# AP_KACA_Controller.net
KiCad netlist of a schematic drawn in EAGLE
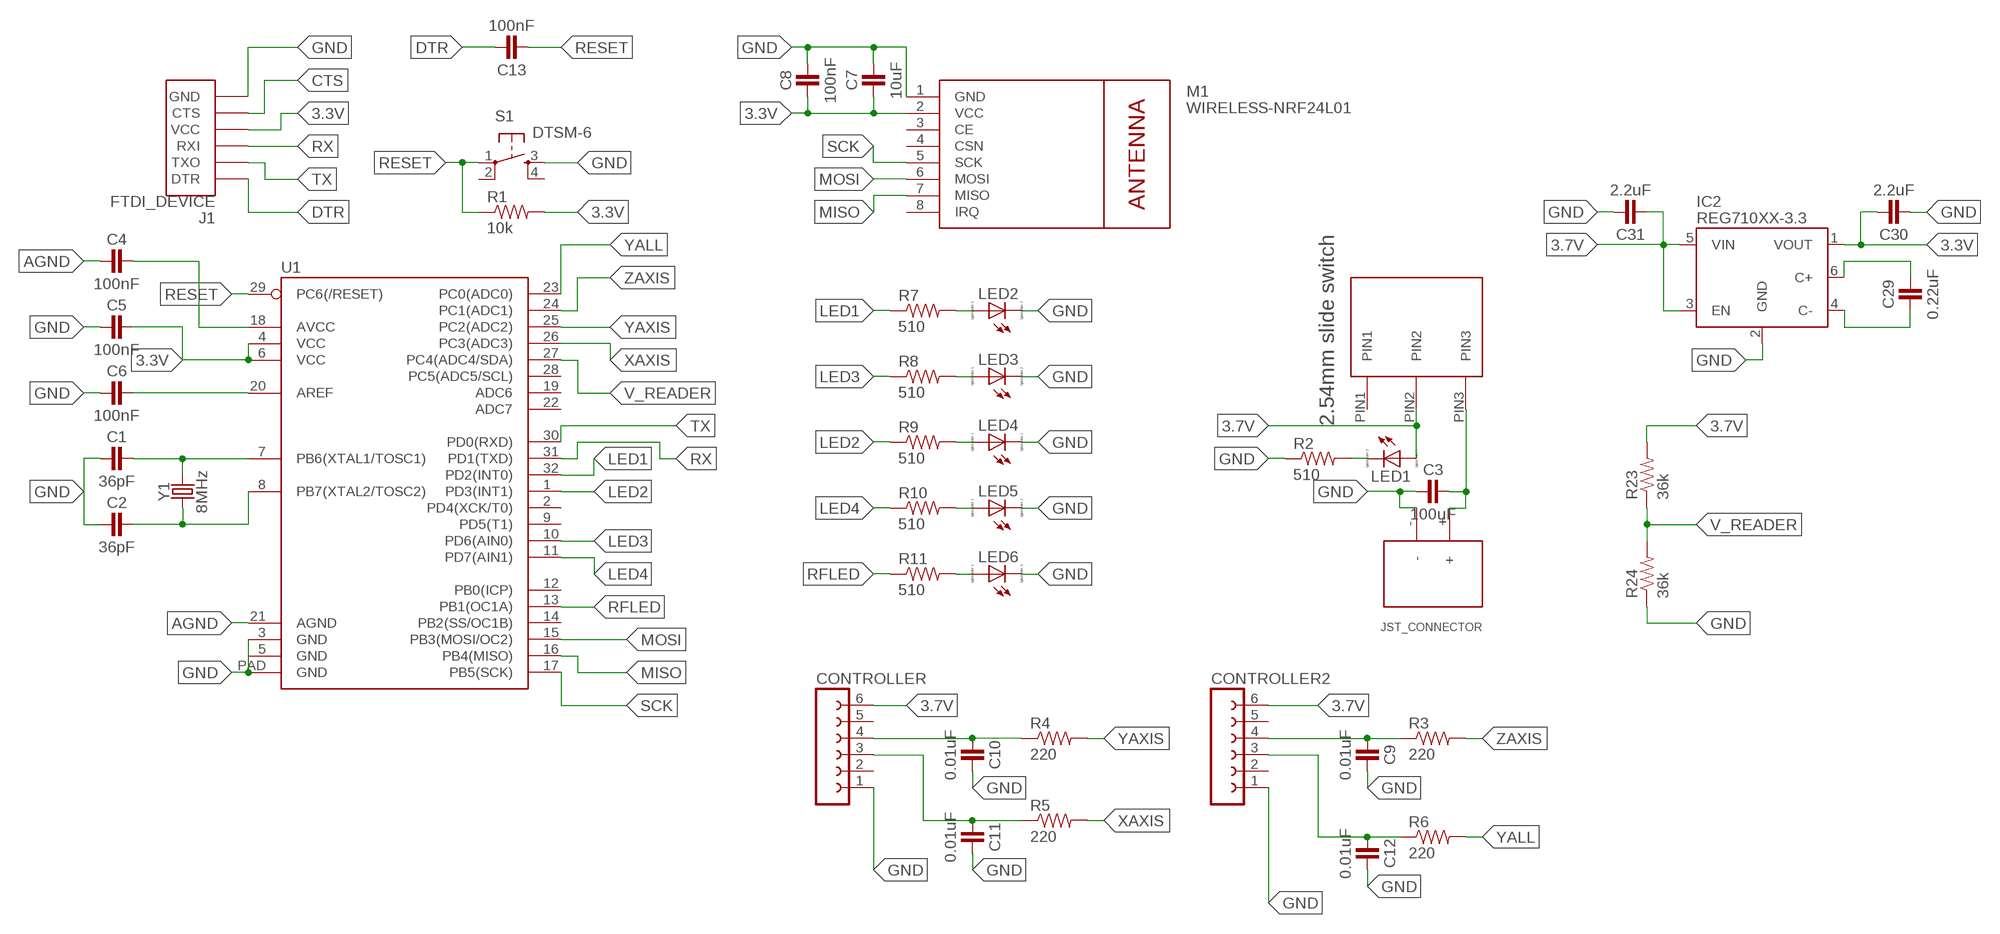
[diagram p0: schematic, sheet 1]

(export (version "E")
  (design (tool "Eeschema 10.0.6"))
  (components
    (comp (ref "C1")
      (value "36pF")
      (footprint "eagle-import:C0603")
      (libsource (lib "eagle-import") (part "CAPACITOR-0603"))
    )
    (comp (ref "C2")
      (value "36pF")
      (footprint "eagle-import:C0603")
      (libsource (lib "eagle-import") (part "CAPACITOR-0603"))
    )
    (comp (ref "C3")
      (value "100uF")
      (footprint "eagle-import:C1206")
      (libsource (lib "eagle-import") (part "CAPACITOR-1206"))
    )
    (comp (ref "C4")
      (value "100nF")
      (footprint "eagle-import:C0603")
      (libsource (lib "eagle-import") (part "CAPACITOR-0603"))
    )
    (comp (ref "C5")
      (value "100nF")
      (footprint "eagle-import:C0603")
      (libsource (lib "eagle-import") (part "CAPACITOR-0603"))
    )
    (comp (ref "C6")
      (value "100nF")
      (footprint "eagle-import:C0603")
      (libsource (lib "eagle-import") (part "CAPACITOR-0603"))
    )
    (comp (ref "C7")
      (value "10uF")
      (footprint "eagle-import:C0603")
      (libsource (lib "eagle-import") (part "CAPACITOR-0603"))
    )
    (comp (ref "C8")
      (value "100nF")
      (footprint "eagle-import:C0603")
      (libsource (lib "eagle-import") (part "CAPACITOR-0603"))
    )
    (comp (ref "C9")
      (value "0.01uF")
      (footprint "eagle-import:C1206")
      (libsource (lib "eagle-import") (part "CAPACITOR-1206"))
    )
    (comp (ref "C10")
      (value "0.01uF")
      (footprint "eagle-import:C1206")
      (libsource (lib "eagle-import") (part "CAPACITOR-1206"))
    )
    (comp (ref "C11")
      (value "0.01uF")
      (footprint "eagle-import:C1206")
      (libsource (lib "eagle-import") (part "CAPACITOR-1206"))
    )
    (comp (ref "C12")
      (value "0.01uF")
      (footprint "eagle-import:C1206")
      (libsource (lib "eagle-import") (part "CAPACITOR-1206"))
    )
    (comp (ref "C13")
      (value "100nF")
      (footprint "eagle-import:C0603")
      (libsource (lib "eagle-import") (part "CAPACITOR-0603"))
    )
    (comp (ref "C29")
      (value "0.22uF")
      (footprint "eagle-import:C1206")
      (libsource (lib "eagle-import") (part "CAPACITOR-1206"))
    )
    (comp (ref "C30")
      (value "2.2uF")
      (footprint "eagle-import:C1206")
      (libsource (lib "eagle-import") (part "CAPACITOR-1206"))
    )
    (comp (ref "C31")
      (value "2.2uF")
      (footprint "eagle-import:C1206")
      (libsource (lib "eagle-import") (part "CAPACITOR-1206"))
    )
    (comp (ref "CONTROLLER")
      (value "FE06-1")
      (footprint "eagle-import:FE06")
      (libsource (lib "eagle-import") (part "FE06-1"))
    )
    (comp (ref "CONTROLLER2")
      (value "FE06-1")
      (footprint "eagle-import:FE06")
      (libsource (lib "eagle-import") (part "FE06-1"))
    )
    (comp (ref "IC2")
      (value "REG710XX-3.3")
      (footprint "eagle-import:SOT23-6")
      (libsource (lib "eagle-import") (part "REG710XX-3.3"))
    )
    (comp (ref "J1")
      (value "FTDI_DEVICE")
      (footprint "eagle-import:FTDI_DEVICE_SIDE")
      (libsource (lib "eagle-import") (part "FTDI_DEVICE"))
    )
    (comp (ref "LED1")
      (value "LED_ESML0603")
      (footprint "eagle-import:LED_SML0603")
      (libsource (lib "eagle-import") (part "LED_ESML0603"))
    )
    (comp (ref "LED2")
      (value "LED_ESML0603")
      (footprint "eagle-import:LED_SML0603")
      (libsource (lib "eagle-import") (part "LED_ESML0603"))
    )
    (comp (ref "LED3")
      (value "LED_ESML0603")
      (footprint "eagle-import:LED_SML0603")
      (libsource (lib "eagle-import") (part "LED_ESML0603"))
    )
    (comp (ref "LED4")
      (value "LED_ESML0603")
      (footprint "eagle-import:LED_SML0603")
      (libsource (lib "eagle-import") (part "LED_ESML0603"))
    )
    (comp (ref "LED5")
      (value "LED_ESML0603")
      (footprint "eagle-import:LED_SML0603")
      (libsource (lib "eagle-import") (part "LED_ESML0603"))
    )
    (comp (ref "LED6")
      (value "LED_ESML0603")
      (footprint "eagle-import:LED_SML0603")
      (libsource (lib "eagle-import") (part "LED_ESML0603"))
    )
    (comp (ref "M1")
      (value "WIRELESS-NRF24L01")
      (footprint "eagle-import:WIRELESS-NRF24L01")
      (libsource (lib "eagle-import") (part "WIRELESS-NRF24L01"))
    )
    (comp (ref "R1")
      (value "10k")
      (footprint "eagle-import:0603")
      (libsource (lib "eagle-import") (part "10.5KOHM1/10W1%(0603)"))
    )
    (comp (ref "R2")
      (value "510")
      (footprint "eagle-import:0603")
      (libsource (lib "eagle-import") (part "10.5KOHM1/10W1%(0603)"))
    )
    (comp (ref "R3")
      (value "220")
      (footprint "eagle-import:0603")
      (libsource (lib "eagle-import") (part "10.5KOHM1/10W1%(0603)"))
    )
    (comp (ref "R4")
      (value "220")
      (footprint "eagle-import:0603")
      (libsource (lib "eagle-import") (part "10.5KOHM1/10W1%(0603)"))
    )
    (comp (ref "R5")
      (value "220")
      (footprint "eagle-import:0603")
      (libsource (lib "eagle-import") (part "10.5KOHM1/10W1%(0603)"))
    )
    (comp (ref "R6")
      (value "220")
      (footprint "eagle-import:0603")
      (libsource (lib "eagle-import") (part "10.5KOHM1/10W1%(0603)"))
    )
    (comp (ref "R7")
      (value "510")
      (footprint "eagle-import:0603")
      (libsource (lib "eagle-import") (part "10.5KOHM1/10W1%(0603)"))
    )
    (comp (ref "R8")
      (value "510")
      (footprint "eagle-import:0603")
      (libsource (lib "eagle-import") (part "10.5KOHM1/10W1%(0603)"))
    )
    (comp (ref "R9")
      (value "510")
      (footprint "eagle-import:0603")
      (libsource (lib "eagle-import") (part "10.5KOHM1/10W1%(0603)"))
    )
    (comp (ref "R10")
      (value "510")
      (footprint "eagle-import:0603")
      (libsource (lib "eagle-import") (part "10.5KOHM1/10W1%(0603)"))
    )
    (comp (ref "R11")
      (value "510")
      (footprint "eagle-import:0603")
      (libsource (lib "eagle-import") (part "10.5KOHM1/10W1%(0603)"))
    )
    (comp (ref "R23")
      (value "36k")
      (footprint "eagle-import:0603")
      (libsource (lib "eagle-import") (part "10.5KOHM1/10W1%(0603)"))
    )
    (comp (ref "R24")
      (value "36k")
      (footprint "eagle-import:0603")
      (libsource (lib "eagle-import") (part "10.5KOHM1/10W1%(0603)"))
    )
    (comp (ref "S1")
      (value "DTSM-6")
      (footprint "eagle-import:DTSM-6")
      (libsource (lib "eagle-import") (part "DTSM-6"))
    )
    (comp (ref "U$1")
      (value "TS02_SWITCH")
      (footprint "eagle-import:TS02_SWITCH")
      (libsource (lib "eagle-import") (part "TS02_SWITCH"))
    )
    (comp (ref "U$2")
      (value "JST_CONNECTOR_FEMALE")
      (footprint "eagle-import:JST_CONNECTOR_FEMALE")
      (libsource (lib "eagle-import") (part "JST_CONNECTOR_FEMALE"))
    )
    (comp (ref "U1")
      (value "ATMEGA328P_MLFMLF32")
      (footprint "eagle-import:MLF32-PAD")
      (libsource (lib "eagle-import") (part "ATMEGA328P_MLFMLF32"))
    )
    (comp (ref "Y1")
      (value "8MHz")
      (footprint "eagle-import:HC49UP")
      (libsource (lib "eagle-import") (part "CRYSTAL-8MHZSMD-HC49UP"))
    )
  )
  (nets
    (net (code "1") (name "3.3V") (class "Default")
      (node (ref "C30") (pin "2") (pinfunction "2_2") (pintype "passive"))
      (node (ref "C5") (pin "2") (pinfunction "2_2") (pintype "passive"))
      (node (ref "C7") (pin "1") (pinfunction "1_1") (pintype "passive"))
      (node (ref "C8") (pin "1") (pinfunction "1_1") (pintype "passive"))
      (node (ref "IC2") (pin "1") (pinfunction "VOUT_1") (pintype "power_in"))
      (node (ref "J1") (pin "P$4") (pinfunction "VCC_P$4") (pintype "bidirectional"))
      (node (ref "M1") (pin "2") (pinfunction "VCC_2") (pintype "power_in"))
      (node (ref "R1") (pin "2") (pinfunction "2_2") (pintype "passive"))
      (node (ref "U1") (pin "4") (pinfunction "VCC_4") (pintype "bidirectional"))
      (node (ref "U1") (pin "6") (pinfunction "VCC_6") (pintype "bidirectional"))
    )
    (net (code "2") (name "3.7V") (class "Default")
      (node (ref "C31") (pin "1") (pinfunction "1_1") (pintype "passive"))
      (node (ref "CONTROLLER") (pin "6") (pinfunction "6_6") (pintype "passive"))
      (node (ref "CONTROLLER2") (pin "6") (pinfunction "6_6") (pintype "passive"))
      (node (ref "IC2") (pin "3") (pinfunction "EN_3") (pintype "passive"))
      (node (ref "IC2") (pin "5") (pinfunction "VIN_5") (pintype "power_in"))
      (node (ref "LED1") (pin "A") (pinfunction "A_A") (pintype "passive"))
      (node (ref "R23") (pin "2") (pinfunction "2_2") (pintype "passive"))
      (node (ref "U$1") (pin "PIN2") (pinfunction "PIN2_PIN2") (pintype "bidirectional"))
    )
    (net (code "3") (name "AGND") (class "Default")
      (node (ref "C4") (pin "1") (pinfunction "1_1") (pintype "passive"))
      (node (ref "U1") (pin "21") (pinfunction "AGND_21") (pintype "bidirectional"))
    )
    (net (code "4") (name "CTS") (class "Default")
      (node (ref "J1") (pin "P$5") (pinfunction "CTS_P$5") (pintype "bidirectional"))
    )
    (net (code "5") (name "DTR") (class "Default")
      (node (ref "C13") (pin "2") (pinfunction "2_2") (pintype "passive"))
      (node (ref "J1") (pin "P$1") (pinfunction "DTR_P$1") (pintype "bidirectional"))
    )
    (net (code "6") (name "GND") (class "Default")
      (node (ref "C1") (pin "1") (pinfunction "1_1") (pintype "passive"))
      (node (ref "C10") (pin "2") (pinfunction "2_2") (pintype "passive"))
      (node (ref "C11") (pin "2") (pinfunction "2_2") (pintype "passive"))
      (node (ref "C12") (pin "2") (pinfunction "2_2") (pintype "passive"))
      (node (ref "C2") (pin "1") (pinfunction "1_1") (pintype "passive"))
      (node (ref "C3") (pin "1") (pinfunction "1_1") (pintype "passive"))
      (node (ref "C30") (pin "1") (pinfunction "1_1") (pintype "passive"))
      (node (ref "C31") (pin "2") (pinfunction "2_2") (pintype "passive"))
      (node (ref "C5") (pin "1") (pinfunction "1_1") (pintype "passive"))
      (node (ref "C6") (pin "1") (pinfunction "1_1") (pintype "passive"))
      (node (ref "C7") (pin "2") (pinfunction "2_2") (pintype "passive"))
      (node (ref "C8") (pin "2") (pinfunction "2_2") (pintype "passive"))
      (node (ref "C9") (pin "2") (pinfunction "2_2") (pintype "passive"))
      (node (ref "CONTROLLER") (pin "1") (pinfunction "1_1") (pintype "passive"))
      (node (ref "CONTROLLER2") (pin "1") (pinfunction "1_1") (pintype "passive"))
      (node (ref "IC2") (pin "2") (pinfunction "GND_2") (pintype "power_in"))
      (node (ref "J1") (pin "P$6") (pinfunction "GND_P$6") (pintype "bidirectional"))
      (node (ref "LED2") (pin "C") (pinfunction "C_C") (pintype "passive"))
      (node (ref "LED3") (pin "C") (pinfunction "C_C") (pintype "passive"))
      (node (ref "LED4") (pin "C") (pinfunction "C_C") (pintype "passive"))
      (node (ref "LED5") (pin "C") (pinfunction "C_C") (pintype "passive"))
      (node (ref "LED6") (pin "C") (pinfunction "C_C") (pintype "passive"))
      (node (ref "M1") (pin "1") (pinfunction "GND_1") (pintype "power_in"))
      (node (ref "R2") (pin "1") (pinfunction "1_1") (pintype "passive"))
      (node (ref "R24") (pin "1") (pinfunction "1_1") (pintype "passive"))
      (node (ref "S1") (pin "3") (pinfunction "3_3") (pintype "passive"))
      (node (ref "U$2") (pin "-") (pinfunction "-_-") (pintype "bidirectional"))
      (node (ref "U1") (pin "3") (pinfunction "GND_3") (pintype "bidirectional"))
      (node (ref "U1") (pin "PAD") (pinfunction "GND_PAD") (pintype "bidirectional"))
    )
    (net (code "7") (name "LED1") (class "Default")
      (node (ref "R7") (pin "1") (pinfunction "1_1") (pintype "passive"))
      (node (ref "U1") (pin "32") (pinfunction "PD2(INT0)_32") (pintype "bidirectional"))
    )
    (net (code "8") (name "LED2") (class "Default")
      (node (ref "R9") (pin "1") (pinfunction "1_1") (pintype "passive"))
      (node (ref "U1") (pin "1") (pinfunction "PD3(INT1)_1") (pintype "bidirectional"))
    )
    (net (code "9") (name "LED3") (class "Default")
      (node (ref "R8") (pin "1") (pinfunction "1_1") (pintype "passive"))
      (node (ref "U1") (pin "10") (pinfunction "PD6(AIN0)_10") (pintype "bidirectional"))
    )
    (net (code "10") (name "LED4") (class "Default")
      (node (ref "R10") (pin "1") (pinfunction "1_1") (pintype "passive"))
      (node (ref "U1") (pin "11") (pinfunction "PD7(AIN1)_11") (pintype "bidirectional"))
    )
    (net (code "11") (name "MISO") (class "Default")
      (node (ref "M1") (pin "7") (pinfunction "MISO_7") (pintype "bidirectional"))
      (node (ref "U1") (pin "16") (pinfunction "PB4(MISO)_16") (pintype "bidirectional"))
    )
    (net (code "12") (name "MOSI") (class "Default")
      (node (ref "M1") (pin "6") (pinfunction "MOSI_6") (pintype "bidirectional"))
      (node (ref "U1") (pin "15") (pinfunction "PB3(MOSI/OC2)_15") (pintype "bidirectional"))
    )
    (net (code "13") (name "Net-(C3-Pad2)") (class "Default")
      (node (ref "C3") (pin "2") (pinfunction "2_2") (pintype "passive"))
      (node (ref "U$1") (pin "PIN3") (pinfunction "PIN3_PIN3") (pintype "bidirectional"))
      (node (ref "U$2") (pin "+") (pinfunction "+_+") (pintype "bidirectional"))
    )
    (net (code "14") (name "Net-(C10-Pad1)") (class "Default")
      (node (ref "C10") (pin "1") (pinfunction "1_1") (pintype "passive"))
      (node (ref "CONTROLLER") (pin "4") (pinfunction "4_4") (pintype "passive"))
      (node (ref "R4") (pin "1") (pinfunction "1_1") (pintype "passive"))
    )
    (net (code "15") (name "Net-(C11-Pad1)") (class "Default")
      (node (ref "C11") (pin "1") (pinfunction "1_1") (pintype "passive"))
      (node (ref "CONTROLLER") (pin "3") (pinfunction "3_3") (pintype "passive"))
      (node (ref "R5") (pin "1") (pinfunction "1_1") (pintype "passive"))
    )
    (net (code "16") (name "Net-(C12-Pad1)") (class "Default")
      (node (ref "C12") (pin "1") (pinfunction "1_1") (pintype "passive"))
      (node (ref "CONTROLLER2") (pin "3") (pinfunction "3_3") (pintype "passive"))
      (node (ref "R6") (pin "1") (pinfunction "1_1") (pintype "passive"))
    )
    (net (code "17") (name "Net-(IC2-C+)") (class "Default")
      (node (ref "C29") (pin "2") (pinfunction "2_2") (pintype "passive"))
      (node (ref "IC2") (pin "6") (pinfunction "C+_6") (pintype "passive"))
    )
    (net (code "18") (name "Net-(IC2-C-)") (class "Default")
      (node (ref "C29") (pin "1") (pinfunction "1_1") (pintype "passive"))
      (node (ref "IC2") (pin "4") (pinfunction "C-_4") (pintype "passive"))
    )
    (net (code "19") (name "Net-(LED1-PadC)") (class "Default")
      (node (ref "LED1") (pin "C") (pinfunction "C_C") (pintype "passive"))
      (node (ref "R2") (pin "2") (pinfunction "2_2") (pintype "passive"))
    )
    (net (code "20") (name "Net-(LED2-PadA)") (class "Default")
      (node (ref "LED2") (pin "A") (pinfunction "A_A") (pintype "passive"))
      (node (ref "R7") (pin "2") (pinfunction "2_2") (pintype "passive"))
    )
    (net (code "21") (name "Net-(LED3-PadA)") (class "Default")
      (node (ref "LED3") (pin "A") (pinfunction "A_A") (pintype "passive"))
      (node (ref "R8") (pin "2") (pinfunction "2_2") (pintype "passive"))
    )
    (net (code "22") (name "Net-(LED4-PadA)") (class "Default")
      (node (ref "LED4") (pin "A") (pinfunction "A_A") (pintype "passive"))
      (node (ref "R9") (pin "2") (pinfunction "2_2") (pintype "passive"))
    )
    (net (code "23") (name "Net-(LED5-PadA)") (class "Default")
      (node (ref "LED5") (pin "A") (pinfunction "A_A") (pintype "passive"))
      (node (ref "R10") (pin "2") (pinfunction "2_2") (pintype "passive"))
    )
    (net (code "24") (name "Net-(LED6-PadA)") (class "Default")
      (node (ref "LED6") (pin "A") (pinfunction "A_A") (pintype "passive"))
      (node (ref "R11") (pin "2") (pinfunction "2_2") (pintype "passive"))
    )
    (net (code "25") (name "Net-(U1-AREF)") (class "Default")
      (node (ref "C6") (pin "2") (pinfunction "2_2") (pintype "passive"))
      (node (ref "U1") (pin "20") (pinfunction "AREF_20") (pintype "bidirectional"))
    )
    (net (code "26") (name "Net-(U1-AVCC)") (class "Default")
      (node (ref "C4") (pin "2") (pinfunction "2_2") (pintype "passive"))
      (node (ref "U1") (pin "18") (pinfunction "AVCC_18") (pintype "bidirectional"))
    )
    (net (code "27") (name "Net-(U1-PB6(XTAL1{slash}TOSC1))") (class "Default")
      (node (ref "C1") (pin "2") (pinfunction "2_2") (pintype "passive"))
      (node (ref "U1") (pin "7") (pinfunction "PB6(XTAL1/TOSC1)_7") (pintype "bidirectional"))
      (node (ref "Y1") (pin "2") (pinfunction "2_2") (pintype "passive"))
    )
    (net (code "28") (name "Net-(U1-PB7(XTAL2{slash}TOSC2))") (class "Default")
      (node (ref "C2") (pin "2") (pinfunction "2_2") (pintype "passive"))
      (node (ref "U1") (pin "8") (pinfunction "PB7(XTAL2/TOSC2)_8") (pintype "bidirectional"))
      (node (ref "Y1") (pin "1") (pinfunction "1_1") (pintype "passive"))
    )
    (net (code "29") (name "RESET") (class "Default")
      (node (ref "C13") (pin "1") (pinfunction "1_1") (pintype "passive"))
      (node (ref "R1") (pin "1") (pinfunction "1_1") (pintype "passive"))
      (node (ref "S1") (pin "1") (pinfunction "1_1") (pintype "passive"))
      (node (ref "U1") (pin "29") (pinfunction "PC6(/RESET)_29") (pintype "bidirectional"))
    )
    (net (code "30") (name "RFLED") (class "Default")
      (node (ref "R11") (pin "1") (pinfunction "1_1") (pintype "passive"))
      (node (ref "U1") (pin "13") (pinfunction "PB1(OC1A)_13") (pintype "bidirectional"))
    )
    (net (code "31") (name "RX") (class "Default")
      (node (ref "J1") (pin "P$3") (pinfunction "RXI_P$3") (pintype "bidirectional"))
      (node (ref "U1") (pin "31") (pinfunction "PD1(TXD)_31") (pintype "bidirectional"))
    )
    (net (code "32") (name "SCK") (class "Default")
      (node (ref "M1") (pin "5") (pinfunction "SCK_5") (pintype "bidirectional"))
      (node (ref "U1") (pin "17") (pinfunction "PB5(SCK)_17") (pintype "bidirectional"))
    )
    (net (code "33") (name "TX") (class "Default")
      (node (ref "J1") (pin "P$2") (pinfunction "TXO_P$2") (pintype "bidirectional"))
      (node (ref "U1") (pin "30") (pinfunction "PD0(RXD)_30") (pintype "bidirectional"))
    )
    (net (code "34") (name "V_READER") (class "Default")
      (node (ref "R23") (pin "1") (pinfunction "1_1") (pintype "passive"))
      (node (ref "R24") (pin "2") (pinfunction "2_2") (pintype "passive"))
      (node (ref "U1") (pin "27") (pinfunction "PC4(ADC4/SDA)_27") (pintype "bidirectional"))
    )
    (net (code "35") (name "XAXIS") (class "Default")
      (node (ref "R5") (pin "2") (pinfunction "2_2") (pintype "passive"))
      (node (ref "U1") (pin "26") (pinfunction "PC3(ADC3)_26") (pintype "bidirectional"))
    )
    (net (code "36") (name "YALL") (class "Default")
      (node (ref "R6") (pin "2") (pinfunction "2_2") (pintype "passive"))
      (node (ref "U1") (pin "23") (pinfunction "PC0(ADC0)_23") (pintype "bidirectional"))
    )
    (net (code "37") (name "YAXIS") (class "Default")
      (node (ref "R4") (pin "2") (pinfunction "2_2") (pintype "passive"))
      (node (ref "U1") (pin "25") (pinfunction "PC2(ADC2)_25") (pintype "bidirectional"))
    )
    (net (code "38") (name "ZAXIS") (class "Default")
      (node (ref "C9") (pin "1") (pinfunction "1_1") (pintype "passive"))
      (node (ref "CONTROLLER2") (pin "4") (pinfunction "4_4") (pintype "passive"))
      (node (ref "R3") (pin "1") (pinfunction "1_1") (pintype "passive"))
      (node (ref "R3") (pin "2") (pinfunction "2_2") (pintype "passive"))
      (node (ref "U1") (pin "24") (pinfunction "PC1(ADC1)_24") (pintype "bidirectional"))
    )
    (net (code "39") (name "unconnected-(CONTROLLER-Pad2)") (class "Default")
      (node (ref "CONTROLLER") (pin "2") (pinfunction "2_2") (pintype "passive"))
    )
    (net (code "40") (name "unconnected-(CONTROLLER-Pad5)") (class "Default")
      (node (ref "CONTROLLER") (pin "5") (pinfunction "5_5") (pintype "passive"))
    )
    (net (code "41") (name "unconnected-(CONTROLLER2-Pad2)") (class "Default")
      (node (ref "CONTROLLER2") (pin "2") (pinfunction "2_2") (pintype "passive"))
    )
    (net (code "42") (name "unconnected-(CONTROLLER2-Pad5)") (class "Default")
      (node (ref "CONTROLLER2") (pin "5") (pinfunction "5_5") (pintype "passive"))
    )
    (net (code "43") (name "unconnected-(M1-CE-Pad3)") (class "Default")
      (node (ref "M1") (pin "3") (pinfunction "CE_3") (pintype "bidirectional"))
    )
    (net (code "44") (name "unconnected-(M1-CSN-Pad4)") (class "Default")
      (node (ref "M1") (pin "4") (pinfunction "CSN_4") (pintype "bidirectional"))
    )
    (net (code "45") (name "unconnected-(M1-IRQ-Pad8)") (class "Default")
      (node (ref "M1") (pin "8") (pinfunction "IRQ_8") (pintype "bidirectional"))
    )
    (net (code "46") (name "unconnected-(S1-Pad2)") (class "Default")
      (node (ref "S1") (pin "2") (pinfunction "2_2") (pintype "passive"))
    )
    (net (code "47") (name "unconnected-(S1-Pad4)") (class "Default")
      (node (ref "S1") (pin "4") (pinfunction "4_4") (pintype "passive"))
    )
    (net (code "48") (name "unconnected-(U$1-PadPIN1)") (class "Default")
      (node (ref "U$1") (pin "PIN1") (pinfunction "PIN1_PIN1") (pintype "bidirectional"))
    )
    (net (code "49") (name "unconnected-(U1-ADC6-Pad19)") (class "Default")
      (node (ref "U1") (pin "19") (pinfunction "ADC6_19") (pintype "bidirectional"))
    )
    (net (code "50") (name "unconnected-(U1-ADC7-Pad22)") (class "Default")
      (node (ref "U1") (pin "22") (pinfunction "ADC7_22") (pintype "bidirectional"))
    )
    (net (code "51") (name "unconnected-(U1-GND-Pad5)") (class "Default")
      (node (ref "U1") (pin "5") (pinfunction "GND_5") (pintype "bidirectional"))
    )
    (net (code "52") (name "unconnected-(U1-PB0(ICP)-Pad12)") (class "Default")
      (node (ref "U1") (pin "12") (pinfunction "PB0(ICP)_12") (pintype "bidirectional"))
    )
    (net (code "53") (name "unconnected-(U1-PB2(SS{slash}OC1B)-Pad14)") (class "Default")
      (node (ref "U1") (pin "14") (pinfunction "PB2(SS/OC1B)_14") (pintype "bidirectional"))
    )
    (net (code "54") (name "unconnected-(U1-PC5(ADC5{slash}SCL)-Pad28)") (class "Default")
      (node (ref "U1") (pin "28") (pinfunction "PC5(ADC5/SCL)_28") (pintype "bidirectional"))
    )
    (net (code "55") (name "unconnected-(U1-PD4(XCK{slash}T0)-Pad2)") (class "Default")
      (node (ref "U1") (pin "2") (pinfunction "PD4(XCK/T0)_2") (pintype "bidirectional"))
    )
    (net (code "56") (name "unconnected-(U1-PD5(T1)-Pad9)") (class "Default")
      (node (ref "U1") (pin "9") (pinfunction "PD5(T1)_9") (pintype "bidirectional"))
    )
  )
)
